# ZHSD-MIPI-CSI2.net
KiCad netlist of a schematic drawn in Altium Designer
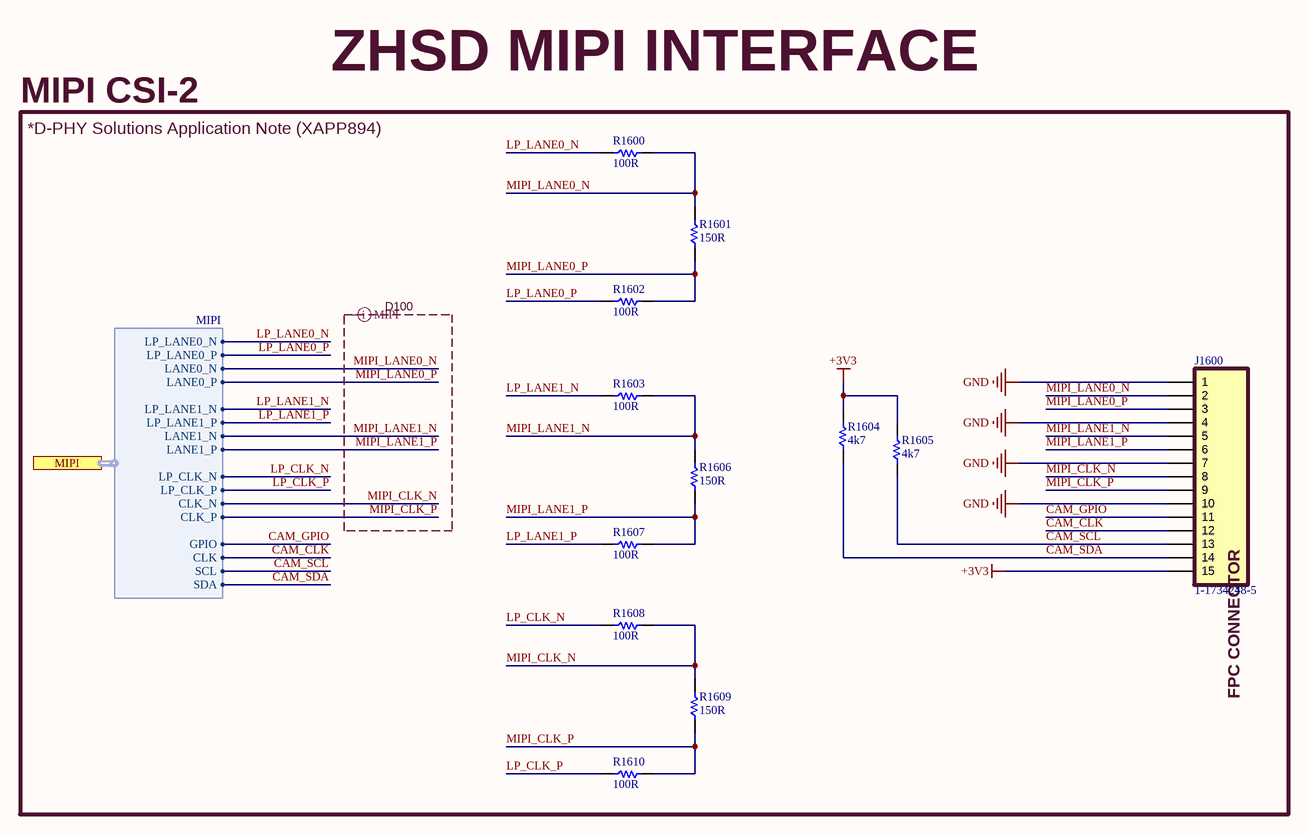
[diagram p0: ZHSD-MIPI-CSI2.SchDoc]

(export (version "E")
  (design (tool "Eeschema 10.0.6"))
  (components
    (comp (ref "J1600")
      (value "1-1734248-5")
      (footprint "TE_1-1734248-5")
      (description "CONN FPC VERT 15POS 1MM SMD")
      (fields (field (name "MANUFACTURER") "TE Connectivity AMP Connectors"))
      (libsource (lib "UK_Library") (part "1-1734248-5"))
    )
    (comp (ref "R1600")
      (value "100R")
      (footprint "0402RESC1005X04N")
      (description "RES 100 OHM 1% 1/16W 0402 (1005)")
      (fields (field (name "MANUFACTURER") "YAGEO") (field (name "MPN") "RC0402FR-07100RL"))
      (libsource (lib "UK_Library") (part "RC0402FR-07100RL"))
    )
    (comp (ref "R1601")
      (value "150R")
      (footprint "0402RESC1005X04N")
      (description "RES 150 OHM 1% 1/16W 0402 (1005)")
      (fields (field (name "MANUFACTURER") "YAGEO") (field (name "MPN") "RC0402FR-07150RL"))
      (libsource (lib "UK_Library") (part "RC0402FR-07150RL"))
    )
    (comp (ref "R1602")
      (value "100R")
      (footprint "0402RESC1005X04N")
      (description "RES 100 OHM 1% 1/16W 0402 (1005)")
      (fields (field (name "MANUFACTURER") "YAGEO") (field (name "MPN") "RC0402FR-07100RL"))
      (libsource (lib "UK_Library") (part "RC0402FR-07100RL"))
    )
    (comp (ref "R1603")
      (value "100R")
      (footprint "0402RESC1005X04N")
      (description "RES 100 OHM 1% 1/16W 0402 (1005)")
      (fields (field (name "MANUFACTURER") "YAGEO") (field (name "MPN") "RC0402FR-07100RL"))
      (libsource (lib "UK_Library") (part "RC0402FR-07100RL"))
    )
    (comp (ref "R1604")
      (value "4k7")
      (footprint "0402RESC1005X04N")
      (description "RES 4.7K OHM 5% 1/16W 0402 (1005)")
      (fields (field (name "MANUFACTURER") "YAGEO") (field (name "MPN") "RT0402FRE0780RL"))
      (libsource (lib "UK_Library") (part "RC0402JR-074K7L"))
    )
    (comp (ref "R1605")
      (value "4k7")
      (footprint "0402RESC1005X04N")
      (description "RES 4.7K OHM 5% 1/16W 0402 (1005)")
      (fields (field (name "MANUFACTURER") "YAGEO") (field (name "MPN") "RT0402FRE0780RL"))
      (libsource (lib "UK_Library") (part "RC0402JR-074K7L"))
    )
    (comp (ref "R1606")
      (value "150R")
      (footprint "0402RESC1005X04N")
      (description "RES 150 OHM 1% 1/16W 0402 (1005)")
      (fields (field (name "MANUFACTURER") "YAGEO") (field (name "MPN") "RC0402FR-07150RL"))
      (libsource (lib "UK_Library") (part "RC0402FR-07150RL"))
    )
    (comp (ref "R1607")
      (value "100R")
      (footprint "0402RESC1005X04N")
      (description "RES 100 OHM 1% 1/16W 0402 (1005)")
      (fields (field (name "MANUFACTURER") "YAGEO") (field (name "MPN") "RC0402FR-07100RL"))
      (libsource (lib "UK_Library") (part "RC0402FR-07100RL"))
    )
    (comp (ref "R1608")
      (value "100R")
      (footprint "0402RESC1005X04N")
      (description "RES 100 OHM 1% 1/16W 0402 (1005)")
      (fields (field (name "MANUFACTURER") "YAGEO") (field (name "MPN") "RC0402FR-07100RL"))
      (libsource (lib "UK_Library") (part "RC0402FR-07100RL"))
    )
    (comp (ref "R1609")
      (value "150R")
      (footprint "0402RESC1005X04N")
      (description "RES 150 OHM 1% 1/16W 0402 (1005)")
      (fields (field (name "MANUFACTURER") "YAGEO") (field (name "MPN") "RC0402FR-07150RL"))
      (libsource (lib "UK_Library") (part "RC0402FR-07150RL"))
    )
    (comp (ref "R1610")
      (value "100R")
      (footprint "0402RESC1005X04N")
      (description "RES 100 OHM 1% 1/16W 0402 (1005)")
      (fields (field (name "MANUFACTURER") "YAGEO") (field (name "MPN") "RC0402FR-07100RL"))
      (libsource (lib "UK_Library") (part "RC0402FR-07100RL"))
    )
  )
  (nets
    (net (code "2") (name "+3V3") (class "Default")
      (node (ref "J1600") (pin "15") (pinfunction "15_15") (pintype "passive"))
      (node (ref "R1604") (pin "2") (pinfunction "2_2") (pintype "passive"))
      (node (ref "R1605") (pin "2") (pinfunction "2_2") (pintype "passive"))
    )
    (net (code "3") (name "/CAM_CLK") (class "Default")
      (node (ref "J1600") (pin "12") (pinfunction "12_12") (pintype "passive"))
    )
    (net (code "4") (name "/CAM_GPIO") (class "Default")
      (node (ref "J1600") (pin "11") (pinfunction "11_11") (pintype "passive"))
    )
    (net (code "5") (name "/CAM_SCL") (class "Default")
      (node (ref "J1600") (pin "13") (pinfunction "13_13") (pintype "passive"))
      (node (ref "R1605") (pin "1") (pinfunction "1_1") (pintype "passive"))
    )
    (net (code "6") (name "/CAM_SDA") (class "Default")
      (node (ref "J1600") (pin "14") (pinfunction "14_14") (pintype "passive"))
      (node (ref "R1604") (pin "1") (pinfunction "1_1") (pintype "passive"))
    )
    (net (code "7") (name "/LP_CLK_N") (class "Default")
      (node (ref "R1608") (pin "2") (pinfunction "2_2") (pintype "passive"))
    )
    (net (code "8") (name "/LP_CLK_P") (class "Default")
      (node (ref "R1610") (pin "2") (pinfunction "2_2") (pintype "passive"))
    )
    (net (code "9") (name "/LP_LANE0_N") (class "Default")
      (node (ref "R1600") (pin "2") (pinfunction "2_2") (pintype "passive"))
    )
    (net (code "10") (name "/LP_LANE0_P") (class "Default")
      (node (ref "R1602") (pin "2") (pinfunction "2_2") (pintype "passive"))
    )
    (net (code "11") (name "/LP_LANE1_N") (class "Default")
      (node (ref "R1603") (pin "2") (pinfunction "2_2") (pintype "passive"))
    )
    (net (code "12") (name "/LP_LANE1_P") (class "Default")
      (node (ref "R1607") (pin "2") (pinfunction "2_2") (pintype "passive"))
    )
    (net (code "13") (name "/MIPI_CLK_N") (class "Default")
      (node (ref "J1600") (pin "8") (pinfunction "8_8") (pintype "passive"))
      (node (ref "R1608") (pin "1") (pinfunction "1_1") (pintype "passive"))
      (node (ref "R1609") (pin "2") (pinfunction "2_2") (pintype "passive"))
    )
    (net (code "14") (name "/MIPI_CLK_P") (class "Default")
      (node (ref "J1600") (pin "9") (pinfunction "9_9") (pintype "passive"))
      (node (ref "R1609") (pin "1") (pinfunction "1_1") (pintype "passive"))
      (node (ref "R1610") (pin "1") (pinfunction "1_1") (pintype "passive"))
    )
    (net (code "15") (name "/MIPI_LANE0_N") (class "Default")
      (node (ref "J1600") (pin "2") (pinfunction "2_2") (pintype "passive"))
      (node (ref "R1600") (pin "1") (pinfunction "1_1") (pintype "passive"))
      (node (ref "R1601") (pin "2") (pinfunction "2_2") (pintype "passive"))
    )
    (net (code "16") (name "/MIPI_LANE0_P") (class "Default")
      (node (ref "J1600") (pin "3") (pinfunction "3_3") (pintype "passive"))
      (node (ref "R1601") (pin "1") (pinfunction "1_1") (pintype "passive"))
      (node (ref "R1602") (pin "1") (pinfunction "1_1") (pintype "passive"))
    )
    (net (code "17") (name "/MIPI_LANE1_N") (class "Default")
      (node (ref "J1600") (pin "5") (pinfunction "5_5") (pintype "passive"))
      (node (ref "R1603") (pin "1") (pinfunction "1_1") (pintype "passive"))
      (node (ref "R1606") (pin "2") (pinfunction "2_2") (pintype "passive"))
    )
    (net (code "18") (name "/MIPI_LANE1_P") (class "Default")
      (node (ref "J1600") (pin "6") (pinfunction "6_6") (pintype "passive"))
      (node (ref "R1606") (pin "1") (pinfunction "1_1") (pintype "passive"))
      (node (ref "R1607") (pin "1") (pinfunction "1_1") (pintype "passive"))
    )
    (net (code "20") (name "GND") (class "Default")
      (node (ref "J1600") (pin "1") (pinfunction "1_1") (pintype "passive"))
      (node (ref "J1600") (pin "10") (pinfunction "10_10") (pintype "passive"))
      (node (ref "J1600") (pin "4") (pinfunction "4_4") (pintype "passive"))
      (node (ref "J1600") (pin "7") (pinfunction "7_7") (pintype "passive"))
    )
  )
)
